# Sheet1.net
KiCad netlist of a schematic drawn in Altium Designer
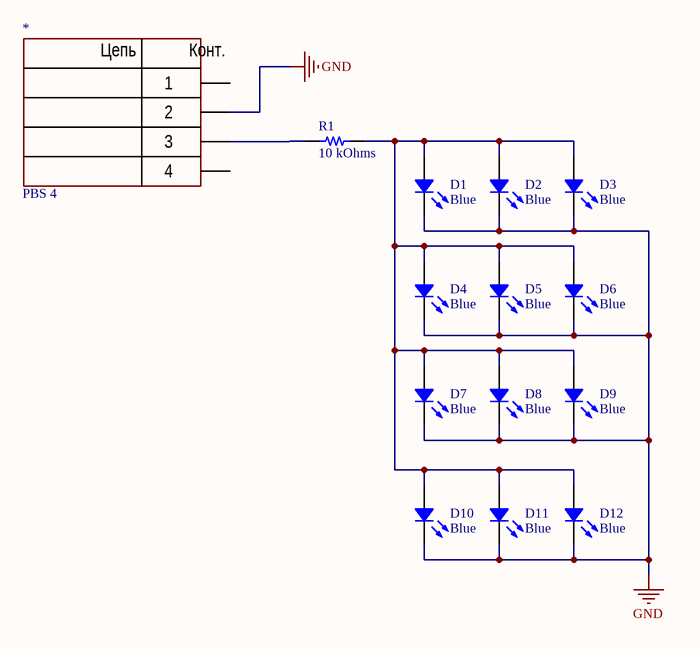
[diagram p0: Sheet1.SchDoc]

(export (version "E")
  (design (tool "Eeschema 10.0.6"))
  (components
    (comp (ref "*") (value "PBS 4") (footprint "PBS-4 CUT") (libsource (lib "liba") (part "PBS 4")))
    (comp (ref "D1")
      (value "Blue")
      (footprint "LED 0603_1608 BLUE")
      (description "LED BLUE CLEAR CHIP SMD")
      (fields (field (name "PART NUMBER") "APT1608VBC/D") (field (name "MANUFACTURER") "Kingbright"))
      (libsource (lib "Celestial Altium Library - altium_library") (part "LED"))
    )
    (comp (ref "D2")
      (value "Blue")
      (footprint "LED 0603_1608 BLUE")
      (description "LED BLUE CLEAR CHIP SMD")
      (fields (field (name "PART NUMBER") "APT1608VBC/D") (field (name "MANUFACTURER") "Kingbright"))
      (libsource (lib "Celestial Altium Library - altium_library") (part "LED"))
    )
    (comp (ref "D3")
      (value "Blue")
      (footprint "LED 0603_1608 BLUE")
      (description "LED BLUE CLEAR CHIP SMD")
      (fields (field (name "PART NUMBER") "APT1608VBC/D") (field (name "MANUFACTURER") "Kingbright"))
      (libsource (lib "Celestial Altium Library - altium_library") (part "LED"))
    )
    (comp (ref "D4")
      (value "Blue")
      (footprint "LED 0603_1608 BLUE")
      (description "LED BLUE CLEAR CHIP SMD")
      (fields (field (name "PART NUMBER") "APT1608VBC/D") (field (name "MANUFACTURER") "Kingbright"))
      (libsource (lib "Celestial Altium Library - altium_library") (part "LED"))
    )
    (comp (ref "D5")
      (value "Blue")
      (footprint "LED 0603_1608 BLUE")
      (description "LED BLUE CLEAR CHIP SMD")
      (fields (field (name "PART NUMBER") "APT1608VBC/D") (field (name "MANUFACTURER") "Kingbright"))
      (libsource (lib "Celestial Altium Library - altium_library") (part "LED"))
    )
    (comp (ref "D6")
      (value "Blue")
      (footprint "LED 0603_1608 BLUE")
      (description "LED BLUE CLEAR CHIP SMD")
      (fields (field (name "PART NUMBER") "APT1608VBC/D") (field (name "MANUFACTURER") "Kingbright"))
      (libsource (lib "Celestial Altium Library - altium_library") (part "LED"))
    )
    (comp (ref "D7")
      (value "Blue")
      (footprint "LED 0603_1608 BLUE")
      (description "LED BLUE CLEAR CHIP SMD")
      (fields (field (name "PART NUMBER") "APT1608VBC/D") (field (name "MANUFACTURER") "Kingbright"))
      (libsource (lib "Celestial Altium Library - altium_library") (part "LED"))
    )
    (comp (ref "D8")
      (value "Blue")
      (footprint "LED 0603_1608 BLUE")
      (description "LED BLUE CLEAR CHIP SMD")
      (fields (field (name "PART NUMBER") "APT1608VBC/D") (field (name "MANUFACTURER") "Kingbright"))
      (libsource (lib "Celestial Altium Library - altium_library") (part "LED"))
    )
    (comp (ref "D9")
      (value "Blue")
      (footprint "LED 0603_1608 BLUE")
      (description "LED BLUE CLEAR CHIP SMD")
      (fields (field (name "PART NUMBER") "APT1608VBC/D") (field (name "MANUFACTURER") "Kingbright"))
      (libsource (lib "Celestial Altium Library - altium_library") (part "LED"))
    )
    (comp (ref "D10")
      (value "Blue")
      (footprint "LED 0603_1608 BLUE")
      (description "LED BLUE CLEAR CHIP SMD")
      (fields (field (name "PART NUMBER") "APT1608VBC/D") (field (name "MANUFACTURER") "Kingbright"))
      (libsource (lib "Celestial Altium Library - altium_library") (part "LED"))
    )
    (comp (ref "D11")
      (value "Blue")
      (footprint "LED 0603_1608 BLUE")
      (description "LED BLUE CLEAR CHIP SMD")
      (fields (field (name "PART NUMBER") "APT1608VBC/D") (field (name "MANUFACTURER") "Kingbright"))
      (libsource (lib "Celestial Altium Library - altium_library") (part "LED"))
    )
    (comp (ref "D12")
      (value "Blue")
      (footprint "LED 0603_1608 BLUE")
      (description "LED BLUE CLEAR CHIP SMD")
      (fields (field (name "PART NUMBER") "APT1608VBC/D") (field (name "MANUFACTURER") "Kingbright"))
      (libsource (lib "Celestial Altium Library - altium_library") (part "LED"))
    )
    (comp (ref "R1")
      (value "10 kOhms")
      (footprint "RES 0603_1608")
      (description "RES 10K OHM 0.1% 1/16W 0603")
      (fields
        (field (name "PART NUMBER") "RNCS0603BKE10K0")
        (field (name "MANUFACTURER") "Stackpole Electronics Inc")
      )
      (libsource (lib "Celestial Altium Library - altium_library") (part "Resistor"))
    )
  )
  (nets
    (net (code "1") (name "GND") (class "Default")
      (node (ref "*") (pin "2") (pinfunction "2_2") (pintype "passive"))
      (node (ref "D1") (pin "2") (pinfunction "2_2") (pintype "passive"))
      (node (ref "D10") (pin "2") (pinfunction "2_2") (pintype "passive"))
      (node (ref "D11") (pin "2") (pinfunction "2_2") (pintype "passive"))
      (node (ref "D12") (pin "2") (pinfunction "2_2") (pintype "passive"))
      (node (ref "D2") (pin "2") (pinfunction "2_2") (pintype "passive"))
      (node (ref "D3") (pin "2") (pinfunction "2_2") (pintype "passive"))
      (node (ref "D4") (pin "2") (pinfunction "2_2") (pintype "passive"))
      (node (ref "D5") (pin "2") (pinfunction "2_2") (pintype "passive"))
      (node (ref "D6") (pin "2") (pinfunction "2_2") (pintype "passive"))
      (node (ref "D7") (pin "2") (pinfunction "2_2") (pintype "passive"))
      (node (ref "D8") (pin "2") (pinfunction "2_2") (pintype "passive"))
      (node (ref "D9") (pin "2") (pinfunction "2_2") (pintype "passive"))
    )
    (net (code "2") (name "Net-(*-Pad3)") (class "Default")
      (node (ref "*") (pin "3") (pinfunction "3_3") (pintype "passive"))
      (node (ref "R1") (pin "1") (pinfunction "1_1") (pintype "passive"))
    )
    (net (code "3") (name "Net-(D1-Pad1)") (class "Default")
      (node (ref "D1") (pin "1") (pinfunction "1_1") (pintype "passive"))
      (node (ref "D10") (pin "1") (pinfunction "1_1") (pintype "passive"))
      (node (ref "D11") (pin "1") (pinfunction "1_1") (pintype "passive"))
      (node (ref "D12") (pin "1") (pinfunction "1_1") (pintype "passive"))
      (node (ref "D2") (pin "1") (pinfunction "1_1") (pintype "passive"))
      (node (ref "D3") (pin "1") (pinfunction "1_1") (pintype "passive"))
      (node (ref "D4") (pin "1") (pinfunction "1_1") (pintype "passive"))
      (node (ref "D5") (pin "1") (pinfunction "1_1") (pintype "passive"))
      (node (ref "D6") (pin "1") (pinfunction "1_1") (pintype "passive"))
      (node (ref "D7") (pin "1") (pinfunction "1_1") (pintype "passive"))
      (node (ref "D8") (pin "1") (pinfunction "1_1") (pintype "passive"))
      (node (ref "D9") (pin "1") (pinfunction "1_1") (pintype "passive"))
      (node (ref "R1") (pin "2") (pinfunction "2_2") (pintype "passive"))
    )
    (net (code "4") (name "unconnected-(*-Pad1)") (class "Default")
      (node (ref "*") (pin "1") (pinfunction "1_1") (pintype "passive"))
    )
    (net (code "5") (name "unconnected-(*-Pad4)") (class "Default")
      (node (ref "*") (pin "4") (pinfunction "4_4") (pintype "passive"))
    )
  )
)
